# sdram_block.net
KiCad netlist of a schematic drawn in Altium Designer
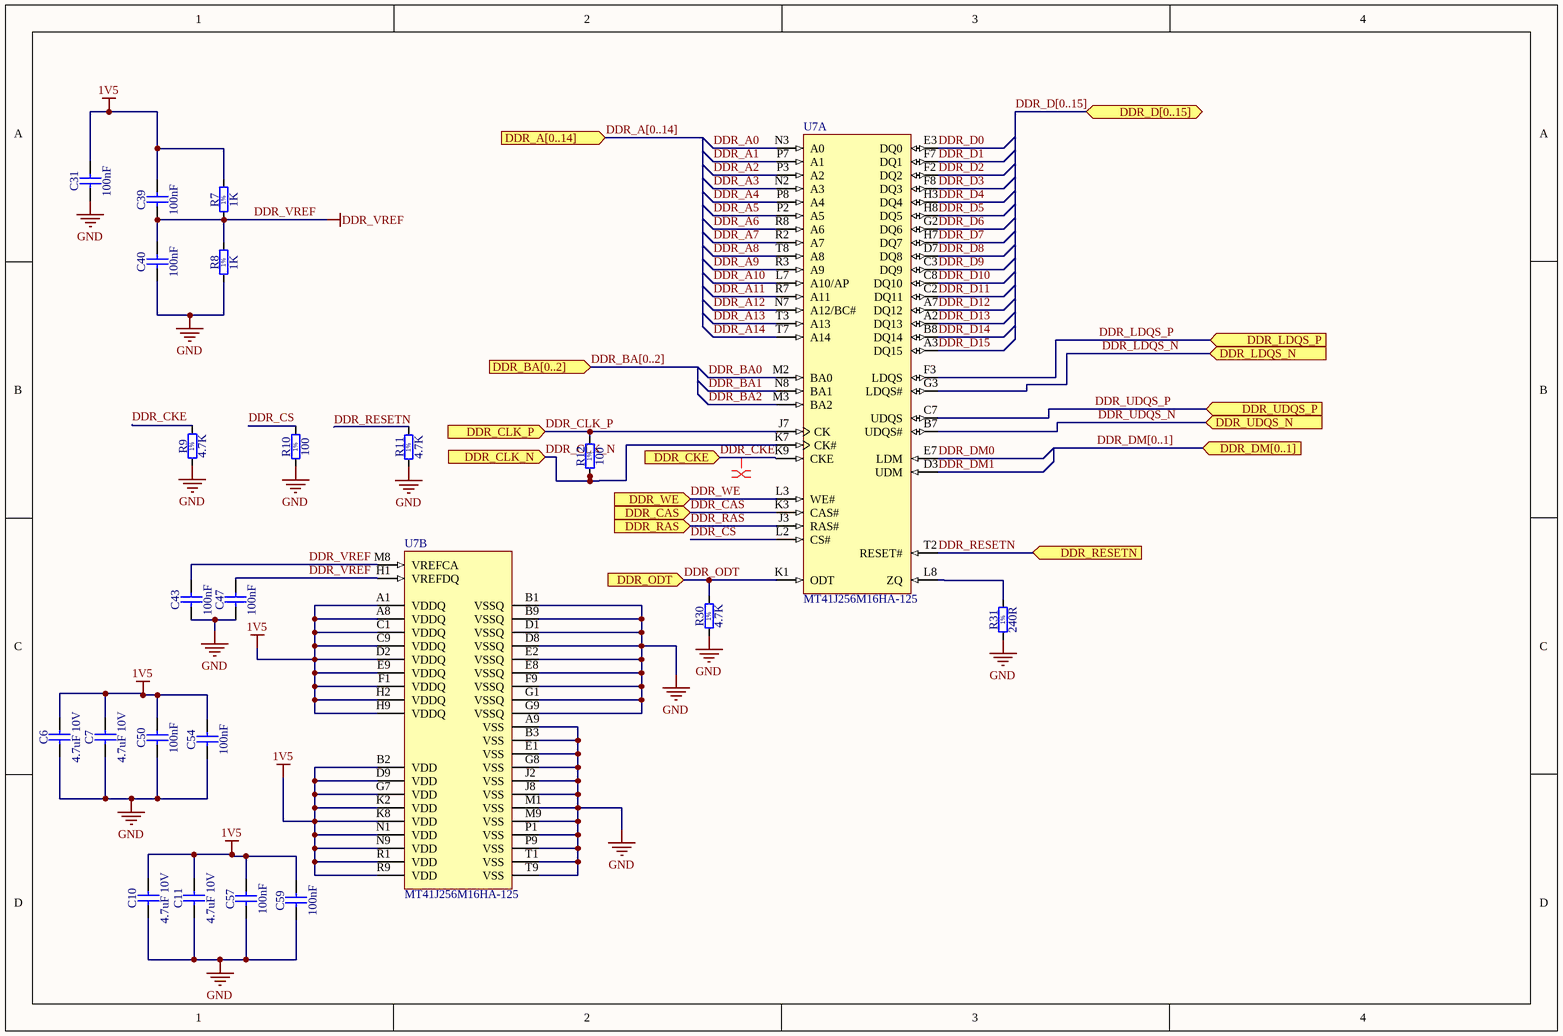
[diagram p0: sdram_block.SchDoc]

(export (version "E")
  (design (tool "Eeschema 10.0.6"))
  (components
    (comp (ref "C6")
      (value "4.7uF 10V")
      (footprint "CAPC2013X100N")
      (description "Non-polarised capacitor")
      (fields
        (field (name "PART NUMBER") "CC0805_1.5NF_50V_5%_C0G")
        (field (name "VOLTAGE") "50V")
        (field (name "AUTHOR") "CERN DEM BC")
      )
      (libsource (lib "Capacitors") (part "Capacitor - non polarized"))
    )
    (comp (ref "C7")
      (value "4.7uF 10V")
      (footprint "CAPC2013X100N")
      (description "Non-polarised capacitor")
      (fields
        (field (name "PART NUMBER") "CC0805_1.5NF_50V_5%_C0G")
        (field (name "VOLTAGE") "50V")
        (field (name "AUTHOR") "CERN DEM BC")
      )
      (libsource (lib "Capacitors") (part "Capacitor - non polarized"))
    )
    (comp (ref "C10")
      (value "4.7uF 10V")
      (footprint "CAPC2013X100N")
      (description "Non-polarised capacitor")
      (fields
        (field (name "PART NUMBER") "CC0805_1.5NF_50V_5%_C0G")
        (field (name "VOLTAGE") "50V")
        (field (name "AUTHOR") "CERN DEM BC")
      )
      (libsource (lib "Capacitors") (part "Capacitor - non polarized"))
    )
    (comp (ref "C11")
      (value "4.7uF 10V")
      (footprint "CAPC2013X100N")
      (description "Non-polarised capacitor")
      (fields
        (field (name "PART NUMBER") "CC0805_1.5NF_50V_5%_C0G")
        (field (name "VOLTAGE") "50V")
        (field (name "AUTHOR") "CERN DEM BC")
      )
      (libsource (lib "Capacitors") (part "Capacitor - non polarized"))
    )
    (comp (ref "C31")
      (value "100nF")
      (footprint "CAPC1005X55N")
      (description "Non-polarised capacitor")
      (fields
        (field (name "PART NUMBER") "CC0402_100NF_16V_10%_X5R")
        (field (name "VOLTAGE") "16V")
        (field (name "AUTHOR") "CERN DEM JLC")
      )
      (libsource (lib "Capacitors") (part "Capacitor - non polarized"))
    )
    (comp (ref "C39")
      (value "100nF")
      (footprint "CAPC1005X55N")
      (description "Non-polarised capacitor")
      (fields
        (field (name "PART NUMBER") "CC0402_100NF_16V_10%_X5R")
        (field (name "VOLTAGE") "16V")
        (field (name "AUTHOR") "CERN DEM JLC")
      )
      (libsource (lib "Capacitors") (part "Capacitor - non polarized"))
    )
    (comp (ref "C40")
      (value "100nF")
      (footprint "CAPC1005X55N")
      (description "Non-polarised capacitor")
      (fields
        (field (name "PART NUMBER") "CC0402_100NF_16V_10%_X5R")
        (field (name "VOLTAGE") "16V")
        (field (name "AUTHOR") "CERN DEM JLC")
      )
      (libsource (lib "Capacitors") (part "Capacitor - non polarized"))
    )
    (comp (ref "C43")
      (value "100nF")
      (footprint "CAPC1005X55N")
      (description "Non-polarised capacitor")
      (fields
        (field (name "PART NUMBER") "CC0402_100NF_16V_10%_X5R")
        (field (name "VOLTAGE") "16V")
        (field (name "AUTHOR") "CERN DEM JLC")
      )
      (libsource (lib "Capacitors") (part "Capacitor - non polarized"))
    )
    (comp (ref "C47")
      (value "100nF")
      (footprint "CAPC1005X55N")
      (description "Non-polarised capacitor")
      (fields
        (field (name "PART NUMBER") "CC0402_100NF_16V_10%_X5R")
        (field (name "VOLTAGE") "16V")
        (field (name "AUTHOR") "CERN DEM JLC")
      )
      (libsource (lib "Capacitors") (part "Capacitor - non polarized"))
    )
    (comp (ref "C50")
      (value "100nF")
      (footprint "CAPC1005X55N")
      (description "Non-polarised capacitor")
      (fields
        (field (name "PART NUMBER") "CC0402_100NF_16V_10%_X5R")
        (field (name "VOLTAGE") "16V")
        (field (name "AUTHOR") "CERN DEM JLC")
      )
      (libsource (lib "Capacitors") (part "Capacitor - non polarized"))
    )
    (comp (ref "C54")
      (value "100nF")
      (footprint "CAPC1005X55N")
      (description "Non-polarised capacitor")
      (fields
        (field (name "PART NUMBER") "CC0402_100NF_16V_10%_X5R")
        (field (name "VOLTAGE") "16V")
        (field (name "AUTHOR") "CERN DEM JLC")
      )
      (libsource (lib "Capacitors") (part "Capacitor - non polarized"))
    )
    (comp (ref "C57")
      (value "100nF")
      (footprint "CAPC1005X55N")
      (description "Non-polarised capacitor")
      (fields
        (field (name "PART NUMBER") "CC0402_100NF_16V_10%_X5R")
        (field (name "VOLTAGE") "16V")
        (field (name "AUTHOR") "CERN DEM JLC")
      )
      (libsource (lib "Capacitors") (part "Capacitor - non polarized"))
    )
    (comp (ref "C59")
      (value "100nF")
      (footprint "CAPC1005X55N")
      (description "Non-polarised capacitor")
      (fields
        (field (name "PART NUMBER") "CC0402_100NF_16V_10%_X5R")
        (field (name "VOLTAGE") "16V")
        (field (name "AUTHOR") "CERN DEM JLC")
      )
      (libsource (lib "Capacitors") (part "Capacitor - non polarized"))
    )
    (comp (ref "R7")
      (value "1K")
      (footprint "RESC1608X55N")
      (description "Resistor - 1%")
      (fields
        (field (name "PART NUMBER") "R0603_100K_1%_0.1W_100PPM")
        (field (name "POWER") "0.1W")
        (field (name "AUTHOR") "CERN DEM JLC")
      )
      (libsource (lib "Resistors") (part "Resistor - 1%"))
    )
    (comp (ref "R8")
      (value "1K")
      (footprint "RESC1608X55N")
      (description "Resistor - 1%")
      (fields
        (field (name "PART NUMBER") "R0603_100K_1%_0.1W_100PPM")
        (field (name "POWER") "0.1W")
        (field (name "AUTHOR") "CERN DEM JLC")
      )
      (libsource (lib "Resistors") (part "Resistor - 1%"))
    )
    (comp (ref "R9")
      (value "4.7K")
      (footprint "RESC1608X55N")
      (description "Resistor - 1%")
      (fields
        (field (name "PART NUMBER") "R0603_100K_1%_0.1W_100PPM")
        (field (name "POWER") "0.1W")
        (field (name "AUTHOR") "CERN DEM JLC")
      )
      (libsource (lib "Resistors") (part "Resistor - 1%"))
    )
    (comp (ref "R10")
      (value "100")
      (footprint "RESC1608X55N")
      (description "Resistor - 1%")
      (fields
        (field (name "PART NUMBER") "R0603_100K_1%_0.1W_100PPM")
        (field (name "POWER") "0.1W")
        (field (name "AUTHOR") "CERN DEM JLC")
      )
      (libsource (lib "Resistors") (part "Resistor - 1%"))
    )
    (comp (ref "R11")
      (value "4.7K")
      (footprint "RESC1608X55N")
      (description "Resistor - 1%")
      (fields
        (field (name "PART NUMBER") "R0603_100K_1%_0.1W_100PPM")
        (field (name "POWER") "0.1W")
        (field (name "AUTHOR") "CERN DEM JLC")
      )
      (libsource (lib "Resistors") (part "Resistor - 1%"))
    )
    (comp (ref "R12")
      (value "100")
      (footprint "RESC1005X40N")
      (description "Resistor - 1%")
      (fields
        (field (name "PART NUMBER") "R0402_100R_1%_0.0625W_100PPM")
        (field (name "POWER") "0.0625W")
        (field (name "AUTHOR") "CERN DEM JLC")
      )
      (libsource (lib "Resistors") (part "Resistor - 1%"))
    )
    (comp (ref "R30")
      (value "4.7K")
      (footprint "RESC1608X55N")
      (description "Resistor - 1%")
      (fields
        (field (name "PART NUMBER") "R0603_100K_1%_0.1W_100PPM")
        (field (name "POWER") "0.1W")
        (field (name "AUTHOR") "CERN DEM JLC")
      )
      (libsource (lib "Resistors") (part "Resistor - 1%"))
    )
    (comp (ref "R31")
      (value "240R")
      (footprint "RESC1608X55N")
      (description "Resistor - 1%")
      (fields
        (field (name "PART NUMBER") "R0603_100K_1%_0.1W_100PPM")
        (field (name "POWER") "0.1W")
        (field (name "AUTHOR") "CERN DEM JLC")
      )
      (libsource (lib "Resistors") (part "Resistor - 1%"))
    )
    (comp (ref "U7")
      (value "MT41J256M16HA-125")
      (footprint "MICT-HA-96")
      (description "4Gb DDR3-1600 SDRAM, 256Mb x 16, 1.25ns, 1.5V, 0 to 95 degC, 96-Ball FBGA, Pb-Free")
      (fields (field (name "VOLTAGE") "1.5V") (field (name "MANUFACTURER") "Micron"))
      (libsource (lib "Micron Memory DDR3 SDRAM") (part "MT41J256M16HA-125"))
    )
  )
  (nets
    (net (code "1") (name "/DDR_A0") (class "Default")
      (node (ref "U7") (pin "N3") (pinfunction "A0_N3") (pintype "input"))
    )
    (net (code "2") (name "/DDR_A1") (class "Default")
      (node (ref "U7") (pin "P7") (pinfunction "A1_P7") (pintype "input"))
    )
    (net (code "3") (name "/DDR_A2") (class "Default")
      (node (ref "U7") (pin "P3") (pinfunction "A2_P3") (pintype "input"))
    )
    (net (code "4") (name "/DDR_A3") (class "Default")
      (node (ref "U7") (pin "N2") (pinfunction "A3_N2") (pintype "input"))
    )
    (net (code "5") (name "/DDR_A4") (class "Default")
      (node (ref "U7") (pin "P8") (pinfunction "A4_P8") (pintype "input"))
    )
    (net (code "6") (name "/DDR_A5") (class "Default")
      (node (ref "U7") (pin "P2") (pinfunction "A5_P2") (pintype "input"))
    )
    (net (code "7") (name "/DDR_A6") (class "Default")
      (node (ref "U7") (pin "R8") (pinfunction "A6_R8") (pintype "input"))
    )
    (net (code "8") (name "/DDR_A7") (class "Default")
      (node (ref "U7") (pin "R2") (pinfunction "A7_R2") (pintype "input"))
    )
    (net (code "9") (name "/DDR_A8") (class "Default")
      (node (ref "U7") (pin "T8") (pinfunction "A8_T8") (pintype "input"))
    )
    (net (code "10") (name "/DDR_A9") (class "Default")
      (node (ref "U7") (pin "R3") (pinfunction "A9_R3") (pintype "input"))
    )
    (net (code "11") (name "/DDR_A10") (class "Default")
      (node (ref "U7") (pin "L7") (pinfunction "A10/AP_L7") (pintype "input"))
    )
    (net (code "12") (name "/DDR_A11") (class "Default")
      (node (ref "U7") (pin "R7") (pinfunction "A11_R7") (pintype "input"))
    )
    (net (code "13") (name "/DDR_A12") (class "Default")
      (node (ref "U7") (pin "N7") (pinfunction "A12/BC#_N7") (pintype "input"))
    )
    (net (code "14") (name "/DDR_A13") (class "Default")
      (node (ref "U7") (pin "T3") (pinfunction "A13_T3") (pintype "input"))
    )
    (net (code "15") (name "/DDR_A14") (class "Default")
      (node (ref "U7") (pin "T7") (pinfunction "A14_T7") (pintype "input"))
    )
    (net (code "17") (name "/DDR_BA0") (class "Default")
      (node (ref "U7") (pin "M2") (pinfunction "BA0_M2") (pintype "input"))
    )
    (net (code "18") (name "/DDR_BA1") (class "Default")
      (node (ref "U7") (pin "N8") (pinfunction "BA1_N8") (pintype "input"))
    )
    (net (code "19") (name "/DDR_BA2") (class "Default")
      (node (ref "U7") (pin "M3") (pinfunction "BA2_M3") (pintype "input"))
    )
    (net (code "21") (name "/DDR_CAS") (class "Default")
      (node (ref "U7") (pin "K3") (pinfunction "CAS#_K3") (pintype "input"))
    )
    (net (code "22") (name "/DDR_CKE") (class "Default")
      (node (ref "R9") (pin "2") (pinfunction "2_2") (pintype "passive"))
      (node (ref "U7") (pin "K9") (pinfunction "CKE_K9") (pintype "input"))
    )
    (net (code "23") (name "/DDR_CLK_N") (class "Default")
      (node (ref "R12") (pin "1") (pinfunction "1_1") (pintype "passive"))
      (node (ref "U7") (pin "K7") (pinfunction "CK#_K7") (pintype "input"))
    )
    (net (code "24") (name "/DDR_CLK_P") (class "Default")
      (node (ref "R12") (pin "2") (pinfunction "2_2") (pintype "passive"))
      (node (ref "U7") (pin "J7") (pinfunction "CK_J7") (pintype "input"))
    )
    (net (code "25") (name "/DDR_CS") (class "Default")
      (node (ref "R10") (pin "2") (pinfunction "2_2") (pintype "passive"))
      (node (ref "U7") (pin "L2") (pinfunction "CS#_L2") (pintype "input"))
    )
    (net (code "26") (name "/DDR_D0") (class "Default")
      (node (ref "U7") (pin "E3") (pinfunction "DQ0_E3") (pintype "bidirectional"))
    )
    (net (code "27") (name "/DDR_D1") (class "Default")
      (node (ref "U7") (pin "F7") (pinfunction "DQ1_F7") (pintype "bidirectional"))
    )
    (net (code "28") (name "/DDR_D2") (class "Default")
      (node (ref "U7") (pin "F2") (pinfunction "DQ2_F2") (pintype "bidirectional"))
    )
    (net (code "29") (name "/DDR_D3") (class "Default")
      (node (ref "U7") (pin "F8") (pinfunction "DQ3_F8") (pintype "bidirectional"))
    )
    (net (code "30") (name "/DDR_D4") (class "Default")
      (node (ref "U7") (pin "H3") (pinfunction "DQ4_H3") (pintype "bidirectional"))
    )
    (net (code "31") (name "/DDR_D5") (class "Default")
      (node (ref "U7") (pin "H8") (pinfunction "DQ5_H8") (pintype "bidirectional"))
    )
    (net (code "32") (name "/DDR_D6") (class "Default")
      (node (ref "U7") (pin "G2") (pinfunction "DQ6_G2") (pintype "bidirectional"))
    )
    (net (code "33") (name "/DDR_D7") (class "Default")
      (node (ref "U7") (pin "H7") (pinfunction "DQ7_H7") (pintype "bidirectional"))
    )
    (net (code "34") (name "/DDR_D8") (class "Default")
      (node (ref "U7") (pin "D7") (pinfunction "DQ8_D7") (pintype "bidirectional"))
    )
    (net (code "35") (name "/DDR_D9") (class "Default")
      (node (ref "U7") (pin "C3") (pinfunction "DQ9_C3") (pintype "bidirectional"))
    )
    (net (code "36") (name "/DDR_D10") (class "Default")
      (node (ref "U7") (pin "C8") (pinfunction "DQ10_C8") (pintype "bidirectional"))
    )
    (net (code "37") (name "/DDR_D11") (class "Default")
      (node (ref "U7") (pin "C2") (pinfunction "DQ11_C2") (pintype "bidirectional"))
    )
    (net (code "38") (name "/DDR_D12") (class "Default")
      (node (ref "U7") (pin "A7") (pinfunction "DQ12_A7") (pintype "bidirectional"))
    )
    (net (code "39") (name "/DDR_D13") (class "Default")
      (node (ref "U7") (pin "A2") (pinfunction "DQ13_A2") (pintype "bidirectional"))
    )
    (net (code "40") (name "/DDR_D14") (class "Default")
      (node (ref "U7") (pin "B8") (pinfunction "DQ14_B8") (pintype "bidirectional"))
    )
    (net (code "41") (name "/DDR_D15") (class "Default")
      (node (ref "U7") (pin "A3") (pinfunction "DQ15_A3") (pintype "bidirectional"))
    )
    (net (code "42") (name "/DDR_DM0") (class "Default")
      (node (ref "U7") (pin "E7") (pinfunction "LDM_E7") (pintype "input"))
    )
    (net (code "43") (name "/DDR_DM1") (class "Default")
      (node (ref "U7") (pin "D3") (pinfunction "UDM_D3") (pintype "input"))
    )
    (net (code "46") (name "/DDR_LDQS_N") (class "Default")
      (node (ref "U7") (pin "G3") (pinfunction "LDQS#_G3") (pintype "bidirectional"))
    )
    (net (code "47") (name "/DDR_LDQS_P") (class "Default")
      (node (ref "U7") (pin "F3") (pinfunction "LDQS_F3") (pintype "bidirectional"))
    )
    (net (code "48") (name "/DDR_ODT") (class "Default")
      (node (ref "R30") (pin "2") (pinfunction "2_2") (pintype "passive"))
      (node (ref "U7") (pin "K1") (pinfunction "ODT_K1") (pintype "input"))
    )
    (net (code "49") (name "/DDR_RAS") (class "Default")
      (node (ref "U7") (pin "J3") (pinfunction "RAS#_J3") (pintype "input"))
    )
    (net (code "50") (name "/DDR_RESETN") (class "Default")
      (node (ref "R11") (pin "2") (pinfunction "2_2") (pintype "passive"))
      (node (ref "U7") (pin "T2") (pinfunction "RESET#_T2") (pintype "input"))
    )
    (net (code "51") (name "/DDR_UDQS_N") (class "Default")
      (node (ref "U7") (pin "B7") (pinfunction "UDQS#_B7") (pintype "bidirectional"))
    )
    (net (code "52") (name "/DDR_UDQS_P") (class "Default")
      (node (ref "U7") (pin "C7") (pinfunction "UDQS_C7") (pintype "bidirectional"))
    )
    (net (code "53") (name "/DDR_WE") (class "Default")
      (node (ref "U7") (pin "L3") (pinfunction "WE#_L3") (pintype "input"))
    )
    (net (code "54") (name "1V5") (class "Default")
      (node (ref "C10") (pin "2") (pinfunction "2_2") (pintype "passive"))
      (node (ref "C11") (pin "2") (pinfunction "2_2") (pintype "passive"))
      (node (ref "C31") (pin "2") (pinfunction "2_2") (pintype "passive"))
      (node (ref "C39") (pin "2") (pinfunction "2_2") (pintype "passive"))
      (node (ref "C50") (pin "2") (pinfunction "2_2") (pintype "passive"))
      (node (ref "C54") (pin "2") (pinfunction "2_2") (pintype "passive"))
      (node (ref "C57") (pin "2") (pinfunction "2_2") (pintype "passive"))
      (node (ref "C59") (pin "2") (pinfunction "2_2") (pintype "passive"))
      (node (ref "C6") (pin "2") (pinfunction "2_2") (pintype "passive"))
      (node (ref "C7") (pin "2") (pinfunction "2_2") (pintype "passive"))
      (node (ref "R7") (pin "2") (pinfunction "2_2") (pintype "passive"))
      (node (ref "U7") (pin "A1") (pinfunction "VDDQ_A1") (pintype "power_in"))
      (node (ref "U7") (pin "A8") (pinfunction "VDDQ_A8") (pintype "power_in"))
      (node (ref "U7") (pin "B2") (pinfunction "VDD_B2") (pintype "power_in"))
      (node (ref "U7") (pin "C1") (pinfunction "VDDQ_C1") (pintype "power_in"))
      (node (ref "U7") (pin "C9") (pinfunction "VDDQ_C9") (pintype "power_in"))
      (node (ref "U7") (pin "D2") (pinfunction "VDDQ_D2") (pintype "power_in"))
      (node (ref "U7") (pin "D9") (pinfunction "VDD_D9") (pintype "power_in"))
      (node (ref "U7") (pin "E9") (pinfunction "VDDQ_E9") (pintype "power_in"))
      (node (ref "U7") (pin "F1") (pinfunction "VDDQ_F1") (pintype "power_in"))
      (node (ref "U7") (pin "G7") (pinfunction "VDD_G7") (pintype "power_in"))
      (node (ref "U7") (pin "H2") (pinfunction "VDDQ_H2") (pintype "power_in"))
      (node (ref "U7") (pin "H9") (pinfunction "VDDQ_H9") (pintype "power_in"))
      (node (ref "U7") (pin "K2") (pinfunction "VDD_K2") (pintype "power_in"))
      (node (ref "U7") (pin "K8") (pinfunction "VDD_K8") (pintype "power_in"))
      (node (ref "U7") (pin "N1") (pinfunction "VDD_N1") (pintype "power_in"))
      (node (ref "U7") (pin "N9") (pinfunction "VDD_N9") (pintype "power_in"))
      (node (ref "U7") (pin "R1") (pinfunction "VDD_R1") (pintype "power_in"))
      (node (ref "U7") (pin "R9") (pinfunction "VDD_R9") (pintype "power_in"))
    )
    (net (code "55") (name "DDR_VREF") (class "Default")
      (node (ref "C39") (pin "1") (pinfunction "1_1") (pintype "passive"))
      (node (ref "C40") (pin "2") (pinfunction "2_2") (pintype "passive"))
      (node (ref "C43") (pin "2") (pinfunction "2_2") (pintype "passive"))
      (node (ref "C47") (pin "2") (pinfunction "2_2") (pintype "passive"))
      (node (ref "R7") (pin "1") (pinfunction "1_1") (pintype "passive"))
      (node (ref "R8") (pin "2") (pinfunction "2_2") (pintype "passive"))
      (node (ref "U7") (pin "H1") (pinfunction "VREFDQ_H1") (pintype "input"))
      (node (ref "U7") (pin "M8") (pinfunction "VREFCA_M8") (pintype "input"))
    )
    (net (code "56") (name "GND") (class "Default")
      (node (ref "C10") (pin "1") (pinfunction "1_1") (pintype "passive"))
      (node (ref "C11") (pin "1") (pinfunction "1_1") (pintype "passive"))
      (node (ref "C31") (pin "1") (pinfunction "1_1") (pintype "passive"))
      (node (ref "C40") (pin "1") (pinfunction "1_1") (pintype "passive"))
      (node (ref "C43") (pin "1") (pinfunction "1_1") (pintype "passive"))
      (node (ref "C47") (pin "1") (pinfunction "1_1") (pintype "passive"))
      (node (ref "C50") (pin "1") (pinfunction "1_1") (pintype "passive"))
      (node (ref "C54") (pin "1") (pinfunction "1_1") (pintype "passive"))
      (node (ref "C57") (pin "1") (pinfunction "1_1") (pintype "passive"))
      (node (ref "C59") (pin "1") (pinfunction "1_1") (pintype "passive"))
      (node (ref "C6") (pin "1") (pinfunction "1_1") (pintype "passive"))
      (node (ref "C7") (pin "1") (pinfunction "1_1") (pintype "passive"))
      (node (ref "R10") (pin "1") (pinfunction "1_1") (pintype "passive"))
      (node (ref "R11") (pin "1") (pinfunction "1_1") (pintype "passive"))
      (node (ref "R30") (pin "1") (pinfunction "1_1") (pintype "passive"))
      (node (ref "R31") (pin "1") (pinfunction "1_1") (pintype "passive"))
      (node (ref "R8") (pin "1") (pinfunction "1_1") (pintype "passive"))
      (node (ref "R9") (pin "1") (pinfunction "1_1") (pintype "passive"))
      (node (ref "U7") (pin "A9") (pinfunction "VSS_A9") (pintype "power_in"))
      (node (ref "U7") (pin "B1") (pinfunction "VSSQ_B1") (pintype "power_in"))
      (node (ref "U7") (pin "B3") (pinfunction "VSS_B3") (pintype "power_in"))
      (node (ref "U7") (pin "B9") (pinfunction "VSSQ_B9") (pintype "power_in"))
      (node (ref "U7") (pin "D1") (pinfunction "VSSQ_D1") (pintype "power_in"))
      (node (ref "U7") (pin "D8") (pinfunction "VSSQ_D8") (pintype "power_in"))
      (node (ref "U7") (pin "E1") (pinfunction "VSS_E1") (pintype "power_in"))
      (node (ref "U7") (pin "E2") (pinfunction "VSSQ_E2") (pintype "power_in"))
      (node (ref "U7") (pin "E8") (pinfunction "VSSQ_E8") (pintype "power_in"))
      (node (ref "U7") (pin "F9") (pinfunction "VSSQ_F9") (pintype "power_in"))
      (node (ref "U7") (pin "G1") (pinfunction "VSSQ_G1") (pintype "power_in"))
      (node (ref "U7") (pin "G8") (pinfunction "VSS_G8") (pintype "power_in"))
      (node (ref "U7") (pin "G9") (pinfunction "VSSQ_G9") (pintype "power_in"))
      (node (ref "U7") (pin "J2") (pinfunction "VSS_J2") (pintype "power_in"))
      (node (ref "U7") (pin "J8") (pinfunction "VSS_J8") (pintype "power_in"))
      (node (ref "U7") (pin "M1") (pinfunction "VSS_M1") (pintype "power_in"))
      (node (ref "U7") (pin "M9") (pinfunction "VSS_M9") (pintype "power_in"))
      (node (ref "U7") (pin "P1") (pinfunction "VSS_P1") (pintype "power_in"))
      (node (ref "U7") (pin "P9") (pinfunction "VSS_P9") (pintype "power_in"))
      (node (ref "U7") (pin "T1") (pinfunction "VSS_T1") (pintype "power_in"))
      (node (ref "U7") (pin "T9") (pinfunction "VSS_T9") (pintype "power_in"))
    )
    (net (code "57") (name "Net-(U7A-ZQ)") (class "Default")
      (node (ref "R31") (pin "2") (pinfunction "2_2") (pintype "passive"))
      (node (ref "U7") (pin "L8") (pinfunction "ZQ_L8") (pintype "input"))
    )
  )
)
